# 555_Synthesizer.net
KiCad netlist of a schematic drawn in EAGLE
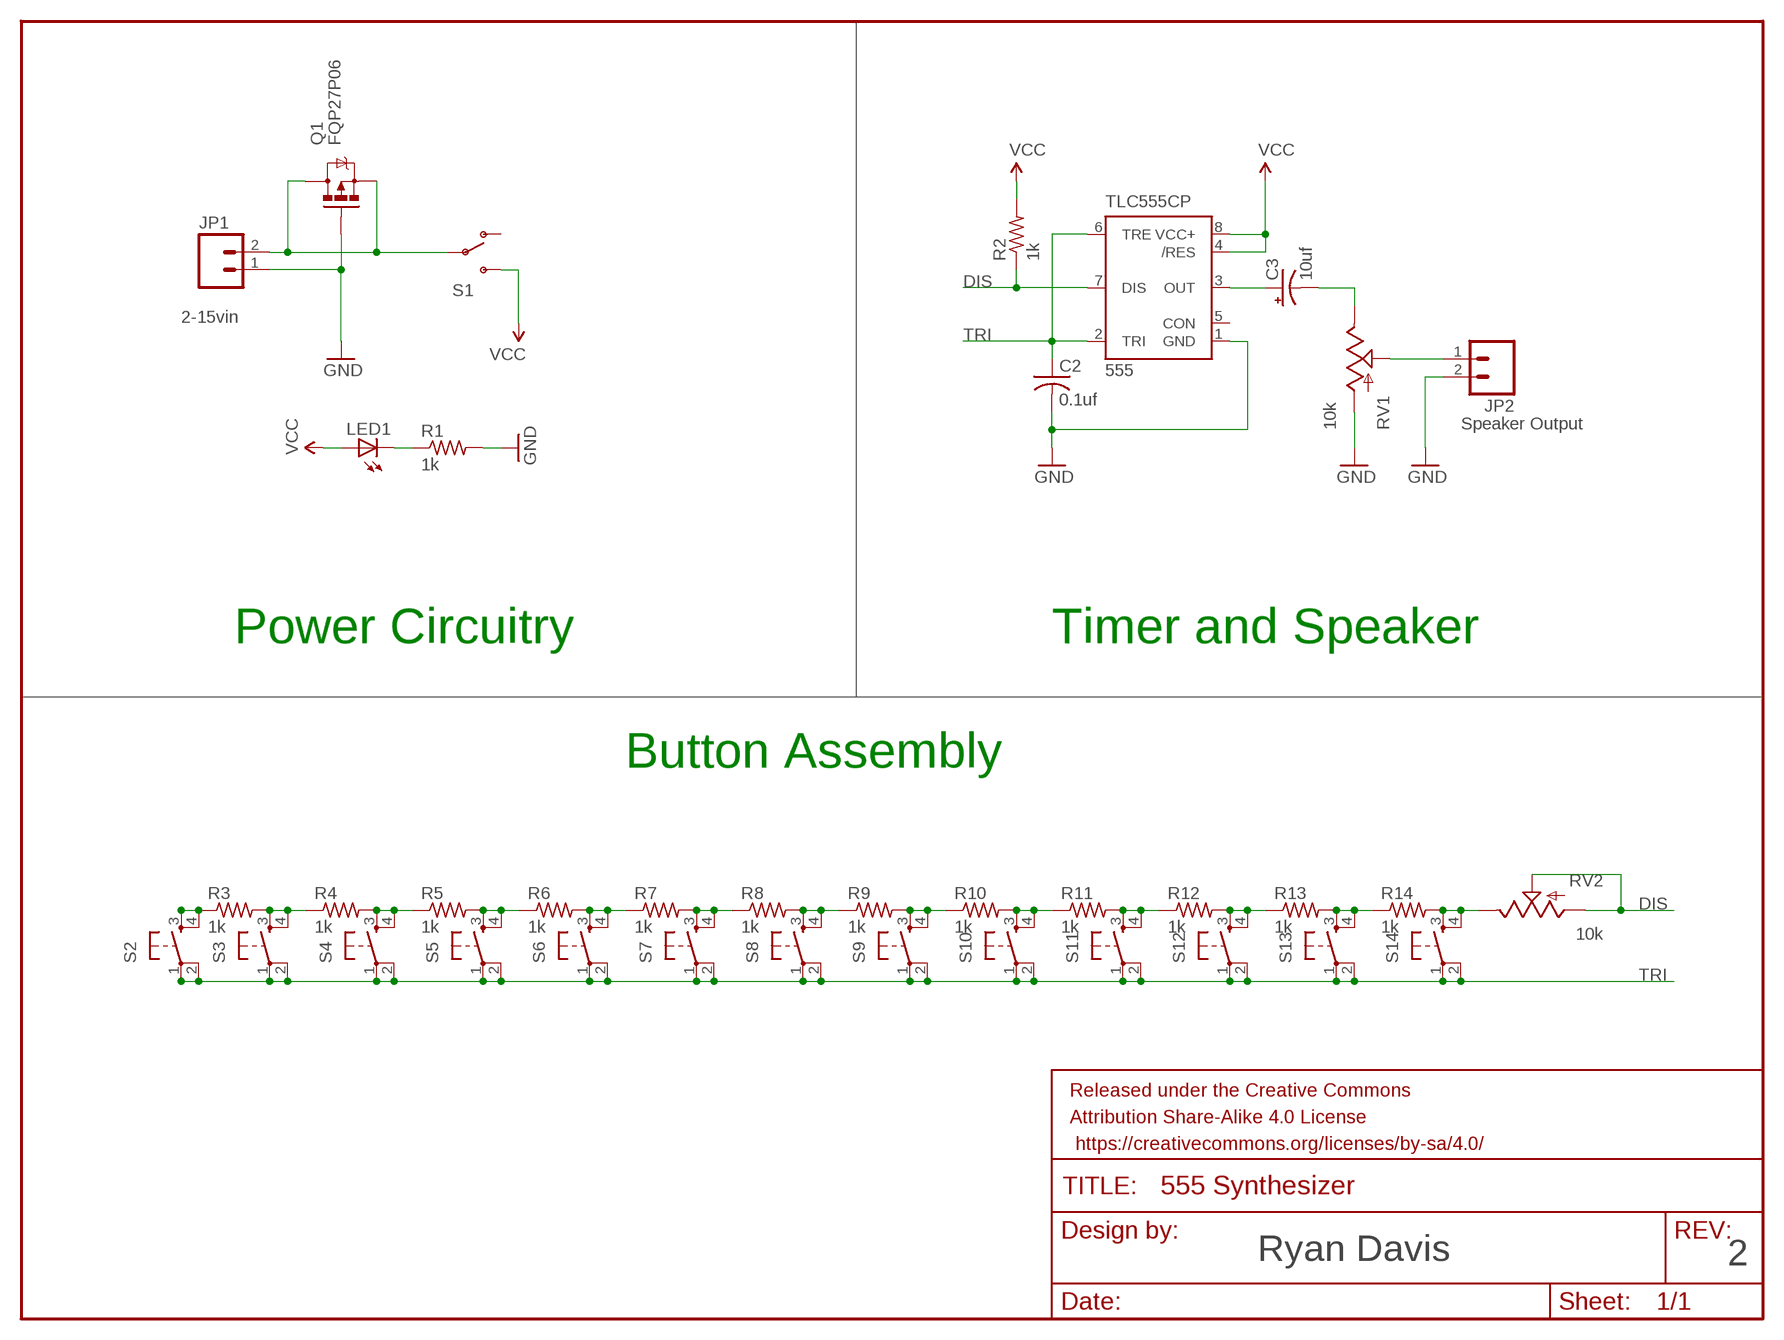
[diagram p0: schematic, sheet 1]

(export (version "E")
  (design (tool "Eeschema 10.0.6"))
  (components
    (comp (ref "C2")
      (value "0.1uf")
      (footprint "eagle-import:C025-025X050")
      (libsource (lib "eagle-import") (part "C-US025-025X050"))
    )
    (comp (ref "C3")
      (value "10uf")
      (footprint "eagle-import:E2,5-6E")
      (libsource (lib "eagle-import") (part "CPOL-USE2,5-6E"))
    )
    (comp (ref "FRAME1")
      (value "FRAME-LETTERNO_PACKAGE")
      (footprint "eagle-import:DUMMY")
      (fields (field (name "DESIGNER") "Nobody"))
      (libsource (lib "eagle-import") (part "FRAME-LETTERNO_PACKAGE"))
    )
    (comp (ref "JP1")
      (value "M023.5MM")
      (footprint "eagle-import:SCREWTERMINAL-3.5MM-2")
      (libsource (lib "eagle-import") (part "M023.5MM"))
    )
    (comp (ref "JP2")
      (value "M023.5MM")
      (footprint "eagle-import:SCREWTERMINAL-3.5MM-2")
      (libsource (lib "eagle-import") (part "M023.5MM"))
    )
    (comp (ref "LED1")
      (value "LED5MM")
      (footprint "eagle-import:LED5MM")
      (libsource (lib "eagle-import") (part "LED5MM"))
    )
    (comp (ref "Q1")
      (value "FQP27P06")
      (footprint "eagle-import:TO220V")
      (libsource (lib "eagle-import") (part "MOSFET-PCHANNELFQP27P06"))
    )
    (comp (ref "R1")
      (value "1k")
      (footprint "eagle-import:0204_7")
      (libsource (lib "eagle-import") (part "R-US_0204/7"))
    )
    (comp (ref "R2")
      (value "1k")
      (footprint "eagle-import:0204_7")
      (libsource (lib "eagle-import") (part "R-US_0204/7"))
    )
    (comp (ref "R3")
      (value "1k")
      (footprint "eagle-import:0204_7")
      (libsource (lib "eagle-import") (part "R-US_0204/7"))
    )
    (comp (ref "R4")
      (value "1k")
      (footprint "eagle-import:0204_7")
      (libsource (lib "eagle-import") (part "R-US_0204/7"))
    )
    (comp (ref "R5")
      (value "1k")
      (footprint "eagle-import:0204_7")
      (libsource (lib "eagle-import") (part "R-US_0204/7"))
    )
    (comp (ref "R6")
      (value "1k")
      (footprint "eagle-import:0204_7")
      (libsource (lib "eagle-import") (part "R-US_0204/7"))
    )
    (comp (ref "R7")
      (value "1k")
      (footprint "eagle-import:0204_7")
      (libsource (lib "eagle-import") (part "R-US_0204/7"))
    )
    (comp (ref "R8")
      (value "1k")
      (footprint "eagle-import:0204_7")
      (libsource (lib "eagle-import") (part "R-US_0204/7"))
    )
    (comp (ref "R9")
      (value "1k")
      (footprint "eagle-import:0204_7")
      (libsource (lib "eagle-import") (part "R-US_0204/7"))
    )
    (comp (ref "R10")
      (value "1k")
      (footprint "eagle-import:0204_7")
      (libsource (lib "eagle-import") (part "R-US_0204/7"))
    )
    (comp (ref "R11")
      (value "1k")
      (footprint "eagle-import:0204_7")
      (libsource (lib "eagle-import") (part "R-US_0204/7"))
    )
    (comp (ref "R12")
      (value "1k")
      (footprint "eagle-import:0204_7")
      (libsource (lib "eagle-import") (part "R-US_0204/7"))
    )
    (comp (ref "R13")
      (value "1k")
      (footprint "eagle-import:0204_7")
      (libsource (lib "eagle-import") (part "R-US_0204/7"))
    )
    (comp (ref "R14")
      (value "1k")
      (footprint "eagle-import:0204_7")
      (libsource (lib "eagle-import") (part "R-US_0204/7"))
    )
    (comp (ref "RV1")
      (value "10k")
      (footprint "eagle-import:ALPS_POT_KIT")
      (libsource (lib "eagle-import") (part "POTALPS-KIT"))
    )
    (comp (ref "RV2")
      (value "10k")
      (footprint "eagle-import:ALPS_POT_KIT")
      (libsource (lib "eagle-import") (part "POTALPS-KIT"))
    )
    (comp (ref "S1")
      (value "SWITCH-SPDTKIT")
      (footprint "eagle-import:SWITCH-SPDT_KIT")
      (libsource (lib "eagle-import") (part "SWITCH-SPDTKIT"))
    )
    (comp (ref "S2")
      (value "TAC_SWITCHPTH")
      (footprint "eagle-import:TACTILE-PTH")
      (libsource (lib "eagle-import") (part "TAC_SWITCHPTH"))
    )
    (comp (ref "S3")
      (value "TAC_SWITCHPTH")
      (footprint "eagle-import:TACTILE-PTH")
      (libsource (lib "eagle-import") (part "TAC_SWITCHPTH"))
    )
    (comp (ref "S4")
      (value "TAC_SWITCHPTH")
      (footprint "eagle-import:TACTILE-PTH")
      (libsource (lib "eagle-import") (part "TAC_SWITCHPTH"))
    )
    (comp (ref "S5")
      (value "TAC_SWITCHPTH")
      (footprint "eagle-import:TACTILE-PTH")
      (libsource (lib "eagle-import") (part "TAC_SWITCHPTH"))
    )
    (comp (ref "S6")
      (value "TAC_SWITCHPTH")
      (footprint "eagle-import:TACTILE-PTH")
      (libsource (lib "eagle-import") (part "TAC_SWITCHPTH"))
    )
    (comp (ref "S7")
      (value "TAC_SWITCHPTH")
      (footprint "eagle-import:TACTILE-PTH")
      (libsource (lib "eagle-import") (part "TAC_SWITCHPTH"))
    )
    (comp (ref "S8")
      (value "TAC_SWITCHPTH")
      (footprint "eagle-import:TACTILE-PTH")
      (libsource (lib "eagle-import") (part "TAC_SWITCHPTH"))
    )
    (comp (ref "S9")
      (value "TAC_SWITCHPTH")
      (footprint "eagle-import:TACTILE-PTH")
      (libsource (lib "eagle-import") (part "TAC_SWITCHPTH"))
    )
    (comp (ref "S10")
      (value "TAC_SWITCHPTH")
      (footprint "eagle-import:TACTILE-PTH")
      (libsource (lib "eagle-import") (part "TAC_SWITCHPTH"))
    )
    (comp (ref "S11")
      (value "TAC_SWITCHPTH")
      (footprint "eagle-import:TACTILE-PTH")
      (libsource (lib "eagle-import") (part "TAC_SWITCHPTH"))
    )
    (comp (ref "S12")
      (value "TAC_SWITCHPTH")
      (footprint "eagle-import:TACTILE-PTH")
      (libsource (lib "eagle-import") (part "TAC_SWITCHPTH"))
    )
    (comp (ref "S13")
      (value "TAC_SWITCHPTH")
      (footprint "eagle-import:TACTILE-PTH")
      (libsource (lib "eagle-import") (part "TAC_SWITCHPTH"))
    )
    (comp (ref "S14")
      (value "TAC_SWITCHPTH")
      (footprint "eagle-import:TACTILE-PTH")
      (libsource (lib "eagle-import") (part "TAC_SWITCHPTH"))
    )
    (comp (ref "TLC555CP")
      (value "555")
      (footprint "eagle-import:DIP08-KIT")
      (libsource (lib "eagle-import") (part "NE555KIT"))
    )
  )
  (nets
    (net (code "1") (name "/DIS") (class "Default")
      (node (ref "R2") (pin "1") (pinfunction "1_1") (pintype "passive"))
      (node (ref "RV2") (pin "P$2") (pinfunction "S_P$2") (pintype "passive"))
      (node (ref "RV2") (pin "P$3") (pinfunction "A_P$3") (pintype "passive"))
      (node (ref "TLC555CP") (pin "7") (pinfunction "DIS_7") (pintype "input"))
    )
    (net (code "2") (name "/TRI") (class "Default")
      (node (ref "C2") (pin "1") (pinfunction "1_1") (pintype "passive"))
      (node (ref "S10") (pin "1") (pinfunction "1_1") (pintype "passive"))
      (node (ref "S10") (pin "2") (pinfunction "2_2") (pintype "passive"))
      (node (ref "S11") (pin "1") (pinfunction "1_1") (pintype "passive"))
      (node (ref "S11") (pin "2") (pinfunction "2_2") (pintype "passive"))
      (node (ref "S12") (pin "1") (pinfunction "1_1") (pintype "passive"))
      (node (ref "S12") (pin "2") (pinfunction "2_2") (pintype "passive"))
      (node (ref "S13") (pin "1") (pinfunction "1_1") (pintype "passive"))
      (node (ref "S13") (pin "2") (pinfunction "2_2") (pintype "passive"))
      (node (ref "S14") (pin "1") (pinfunction "1_1") (pintype "passive"))
      (node (ref "S14") (pin "2") (pinfunction "2_2") (pintype "passive"))
      (node (ref "S2") (pin "1") (pinfunction "1_1") (pintype "passive"))
      (node (ref "S2") (pin "2") (pinfunction "2_2") (pintype "passive"))
      (node (ref "S3") (pin "1") (pinfunction "1_1") (pintype "passive"))
      (node (ref "S3") (pin "2") (pinfunction "2_2") (pintype "passive"))
      (node (ref "S4") (pin "1") (pinfunction "1_1") (pintype "passive"))
      (node (ref "S4") (pin "2") (pinfunction "2_2") (pintype "passive"))
      (node (ref "S5") (pin "1") (pinfunction "1_1") (pintype "passive"))
      (node (ref "S5") (pin "2") (pinfunction "2_2") (pintype "passive"))
      (node (ref "S6") (pin "1") (pinfunction "1_1") (pintype "passive"))
      (node (ref "S6") (pin "2") (pinfunction "2_2") (pintype "passive"))
      (node (ref "S7") (pin "1") (pinfunction "1_1") (pintype "passive"))
      (node (ref "S7") (pin "2") (pinfunction "2_2") (pintype "passive"))
      (node (ref "S8") (pin "1") (pinfunction "1_1") (pintype "passive"))
      (node (ref "S8") (pin "2") (pinfunction "2_2") (pintype "passive"))
      (node (ref "S9") (pin "1") (pinfunction "1_1") (pintype "passive"))
      (node (ref "S9") (pin "2") (pinfunction "2_2") (pintype "passive"))
      (node (ref "TLC555CP") (pin "2") (pinfunction "TRI_2") (pintype "input"))
      (node (ref "TLC555CP") (pin "6") (pinfunction "TRE_6") (pintype "input"))
    )
    (net (code "3") (name "GND") (class "Default")
      (node (ref "C2") (pin "2") (pinfunction "2_2") (pintype "passive"))
      (node (ref "JP1") (pin "1") (pinfunction "1_1") (pintype "passive"))
      (node (ref "JP2") (pin "2") (pinfunction "2_2") (pintype "passive"))
      (node (ref "Q1") (pin "1") (pinfunction "G_1") (pintype "passive"))
      (node (ref "R1") (pin "2") (pinfunction "2_2") (pintype "passive"))
      (node (ref "RV1") (pin "P$3") (pinfunction "A_P$3") (pintype "passive"))
      (node (ref "TLC555CP") (pin "1") (pinfunction "GND_1") (pintype "power_in"))
    )
    (net (code "4") (name "Net-(LED1-C)") (class "Default")
      (node (ref "LED1") (pin "K") (pinfunction "C_K") (pintype "passive"))
      (node (ref "R1") (pin "1") (pinfunction "1_1") (pintype "passive"))
    )
    (net (code "5") (name "Net-(Q1-D)") (class "Default")
      (node (ref "JP1") (pin "2") (pinfunction "2_2") (pintype "passive"))
      (node (ref "Q1") (pin "2") (pinfunction "D_2") (pintype "passive"))
      (node (ref "Q1") (pin "3") (pinfunction "S_3") (pintype "passive"))
      (node (ref "S1") (pin "2") (pinfunction "P_2") (pintype "passive"))
    )
    (net (code "6") (name "Net-(R3-Pad1)") (class "Default")
      (node (ref "R3") (pin "1") (pinfunction "1_1") (pintype "passive"))
      (node (ref "S2") (pin "3") (pinfunction "3_3") (pintype "passive"))
      (node (ref "S2") (pin "4") (pinfunction "4_4") (pintype "passive"))
    )
    (net (code "7") (name "Net-(R3-Pad2)") (class "Default")
      (node (ref "R3") (pin "2") (pinfunction "2_2") (pintype "passive"))
      (node (ref "R4") (pin "1") (pinfunction "1_1") (pintype "passive"))
      (node (ref "S3") (pin "3") (pinfunction "3_3") (pintype "passive"))
      (node (ref "S3") (pin "4") (pinfunction "4_4") (pintype "passive"))
    )
    (net (code "8") (name "Net-(R4-Pad2)") (class "Default")
      (node (ref "R4") (pin "2") (pinfunction "2_2") (pintype "passive"))
      (node (ref "R5") (pin "1") (pinfunction "1_1") (pintype "passive"))
      (node (ref "S4") (pin "3") (pinfunction "3_3") (pintype "passive"))
      (node (ref "S4") (pin "4") (pinfunction "4_4") (pintype "passive"))
    )
    (net (code "9") (name "Net-(R5-Pad2)") (class "Default")
      (node (ref "R5") (pin "2") (pinfunction "2_2") (pintype "passive"))
      (node (ref "R6") (pin "1") (pinfunction "1_1") (pintype "passive"))
      (node (ref "S5") (pin "3") (pinfunction "3_3") (pintype "passive"))
      (node (ref "S5") (pin "4") (pinfunction "4_4") (pintype "passive"))
    )
    (net (code "10") (name "Net-(R6-Pad2)") (class "Default")
      (node (ref "R6") (pin "2") (pinfunction "2_2") (pintype "passive"))
      (node (ref "R7") (pin "1") (pinfunction "1_1") (pintype "passive"))
      (node (ref "S6") (pin "3") (pinfunction "3_3") (pintype "passive"))
      (node (ref "S6") (pin "4") (pinfunction "4_4") (pintype "passive"))
    )
    (net (code "11") (name "Net-(R7-Pad2)") (class "Default")
      (node (ref "R7") (pin "2") (pinfunction "2_2") (pintype "passive"))
      (node (ref "R8") (pin "1") (pinfunction "1_1") (pintype "passive"))
      (node (ref "S7") (pin "3") (pinfunction "3_3") (pintype "passive"))
      (node (ref "S7") (pin "4") (pinfunction "4_4") (pintype "passive"))
    )
    (net (code "12") (name "Net-(R8-Pad2)") (class "Default")
      (node (ref "R8") (pin "2") (pinfunction "2_2") (pintype "passive"))
      (node (ref "R9") (pin "1") (pinfunction "1_1") (pintype "passive"))
      (node (ref "S8") (pin "3") (pinfunction "3_3") (pintype "passive"))
      (node (ref "S8") (pin "4") (pinfunction "4_4") (pintype "passive"))
    )
    (net (code "13") (name "Net-(R10-Pad1)") (class "Default")
      (node (ref "R10") (pin "1") (pinfunction "1_1") (pintype "passive"))
      (node (ref "R9") (pin "2") (pinfunction "2_2") (pintype "passive"))
      (node (ref "S9") (pin "3") (pinfunction "3_3") (pintype "passive"))
      (node (ref "S9") (pin "4") (pinfunction "4_4") (pintype "passive"))
    )
    (net (code "14") (name "Net-(R10-Pad2)") (class "Default")
      (node (ref "R10") (pin "2") (pinfunction "2_2") (pintype "passive"))
      (node (ref "R11") (pin "1") (pinfunction "1_1") (pintype "passive"))
      (node (ref "S10") (pin "3") (pinfunction "3_3") (pintype "passive"))
      (node (ref "S10") (pin "4") (pinfunction "4_4") (pintype "passive"))
    )
    (net (code "15") (name "Net-(R11-Pad2)") (class "Default")
      (node (ref "R11") (pin "2") (pinfunction "2_2") (pintype "passive"))
      (node (ref "R12") (pin "1") (pinfunction "1_1") (pintype "passive"))
      (node (ref "S11") (pin "3") (pinfunction "3_3") (pintype "passive"))
      (node (ref "S11") (pin "4") (pinfunction "4_4") (pintype "passive"))
    )
    (net (code "16") (name "Net-(R12-Pad2)") (class "Default")
      (node (ref "R12") (pin "2") (pinfunction "2_2") (pintype "passive"))
      (node (ref "R13") (pin "1") (pinfunction "1_1") (pintype "passive"))
      (node (ref "S12") (pin "3") (pinfunction "3_3") (pintype "passive"))
      (node (ref "S12") (pin "4") (pinfunction "4_4") (pintype "passive"))
    )
    (net (code "17") (name "Net-(R13-Pad2)") (class "Default")
      (node (ref "R13") (pin "2") (pinfunction "2_2") (pintype "passive"))
      (node (ref "R14") (pin "1") (pinfunction "1_1") (pintype "passive"))
      (node (ref "S13") (pin "3") (pinfunction "3_3") (pintype "passive"))
      (node (ref "S13") (pin "4") (pinfunction "4_4") (pintype "passive"))
    )
    (net (code "18") (name "Net-(RV1-E)") (class "Default")
      (node (ref "C3") (pin "-") (pinfunction "-_-") (pintype "passive"))
      (node (ref "RV1") (pin "P$1") (pinfunction "E_P$1") (pintype "passive"))
    )
    (net (code "19") (name "Net-(RV1-S)") (class "Default")
      (node (ref "JP2") (pin "1") (pinfunction "1_1") (pintype "passive"))
      (node (ref "RV1") (pin "P$2") (pinfunction "S_P$2") (pintype "passive"))
    )
    (net (code "20") (name "Net-(RV2-E)") (class "Default")
      (node (ref "R14") (pin "2") (pinfunction "2_2") (pintype "passive"))
      (node (ref "RV2") (pin "P$1") (pinfunction "E_P$1") (pintype "passive"))
      (node (ref "S14") (pin "3") (pinfunction "3_3") (pintype "passive"))
      (node (ref "S14") (pin "4") (pinfunction "4_4") (pintype "passive"))
    )
    (net (code "21") (name "Net-(TLC555CP-OUT)") (class "Default")
      (node (ref "C3") (pin "+") (pinfunction "+_+") (pintype "passive"))
      (node (ref "TLC555CP") (pin "3") (pinfunction "OUT_3") (pintype "output"))
    )
    (net (code "22") (name "VCC") (class "Default")
      (node (ref "LED1") (pin "A") (pinfunction "A_A") (pintype "passive"))
      (node (ref "R2") (pin "2") (pinfunction "2_2") (pintype "passive"))
      (node (ref "S1") (pin "3") (pinfunction "S_3") (pintype "passive"))
      (node (ref "TLC555CP") (pin "4") (pinfunction "/RES_4") (pintype "input"))
      (node (ref "TLC555CP") (pin "8") (pinfunction "VCC+_8") (pintype "power_in"))
    )
    (net (code "23") (name "unconnected-(S1-O-Pad1)") (class "Default")
      (node (ref "S1") (pin "1") (pinfunction "O_1") (pintype "passive"))
    )
    (net (code "24") (name "unconnected-(TLC555CP-CON-Pad5)") (class "Default")
      (node (ref "TLC555CP") (pin "5") (pinfunction "CON_5") (pintype "input"))
    )
  )
)
